# 6_laser_driver.net
KiCad netlist of a schematic drawn in Altium Designer
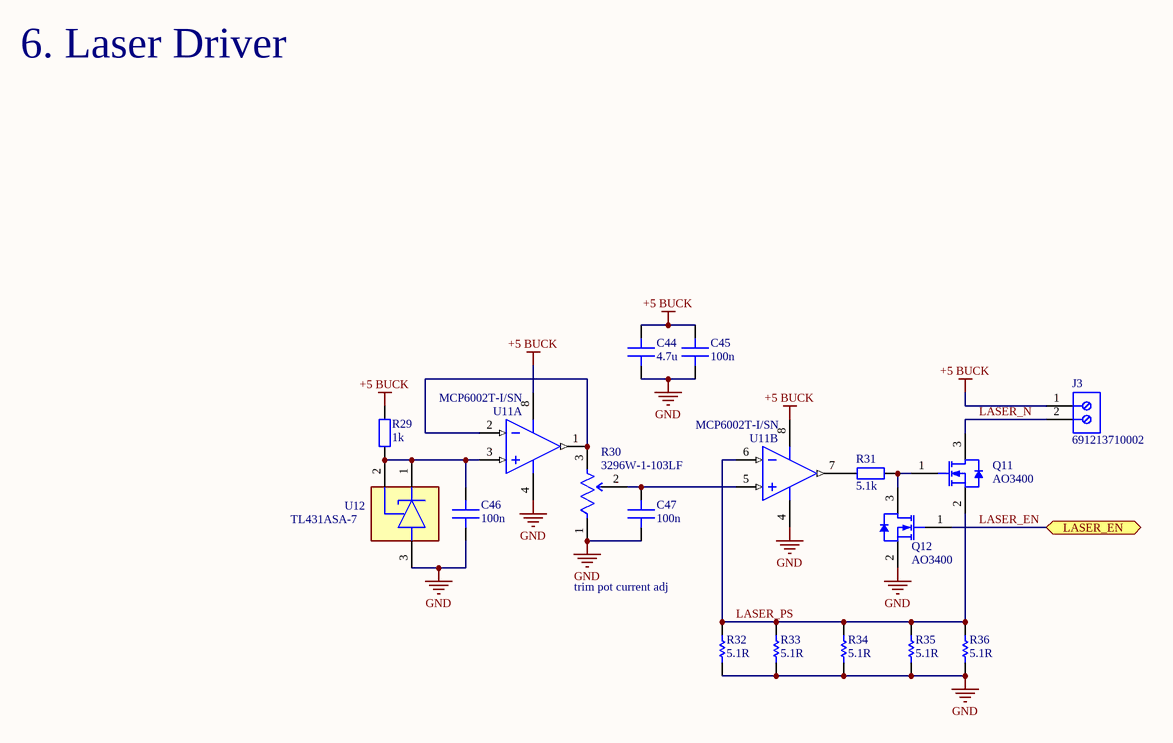
[diagram p0: 6_laser driver.SchDoc]

(export (version "E")
  (design (tool "Eeschema 10.0.6"))
  (components
    (comp (ref "C44")
      (value "4.7u")
      (footprint "IPC C C0603 NO SILK")
      (libsource (lib "JLCPCB Library") (part "Generic CAP 0603"))
    )
    (comp (ref "C45")
      (value "100n")
      (footprint "IPC C C0402 NO SILK")
      (libsource (lib "JLCPCB Library") (part "Generic CAP 0402"))
    )
    (comp (ref "C46")
      (value "100n")
      (footprint "IPC C C0402 NO SILK")
      (libsource (lib "JLCPCB Library") (part "Generic CAP 0402"))
    )
    (comp (ref "C47")
      (value "100n")
      (footprint "IPC C C0402 NO SILK")
      (libsource (lib "JLCPCB Library") (part "Generic CAP 0402"))
    )
    (comp (ref "J3")
      (value "691213710002")
      (footprint "691213710002")
      (fields (field (name "VOLTAGE") "300V"))
      (libsource (lib "Altium Content Vault") (part "TBL - 1R - 02P - Screw"))
    )
    (comp (ref "Q11")
      (value "AO3400")
      (footprint "AO-SOT23-3_V")
      (description "N-channel Enhancement Mode Field-Effect Transistor; 5.8A/30V")
      (fields (field (name "MANUFACTURER") "Alpha and Omega"))
      (libsource (lib "Altium Content Vault") (part "AO-NEMOS-G1S2D3-3"))
    )
    (comp (ref "Q12")
      (value "AO3400")
      (footprint "AO-SOT23-3_V")
      (description "N-channel Enhancement Mode Field-Effect Transistor; 5.8A/30V")
      (fields (field (name "MANUFACTURER") "Alpha and Omega"))
      (libsource (lib "Altium Content Vault") (part "AO-NEMOS-G1S2D3-3"))
    )
    (comp (ref "R29")
      (value "1k")
      (footprint "IPC C R0402 NO SILK")
      (libsource (lib "JLCPCB Library") (part "Generic RES 0402"))
    )
    (comp (ref "R30")
      (value "3296W-1-103LF")
      (footprint "FP-3296W-MFG")
      (description "TRIMMER 10K OHM 0.5W PC PIN TOP")
      (fields (field (name "TOLERANCE") "10%"))
      (libsource (lib "Altium Content Vault") (part "2dcfd2547301a7d3209a5e99acfd772"))
    )
    (comp (ref "R31")
      (value "5.1k")
      (footprint "IPC C R0402 NO SILK")
      (libsource (lib "JLCPCB Library") (part "Generic RES 0402"))
    )
    (comp (ref "R32")
      (value "5.1R")
      (footprint "RESC2013X70X40LL20T20")
      (fields (field (name "PART NUMBER") "ERJ-6GEYJ5R1V") (field (name "MANUFACTURER") "Panasonic"))
      (libsource (lib "Altium Content Vault") (part "RES"))
    )
    (comp (ref "R33")
      (value "5.1R")
      (footprint "RESC2013X70X40LL20T20")
      (fields (field (name "PART NUMBER") "ERJ-6GEYJ5R1V") (field (name "MANUFACTURER") "Panasonic"))
      (libsource (lib "Altium Content Vault") (part "RES"))
    )
    (comp (ref "R34")
      (value "5.1R")
      (footprint "RESC2013X70X40LL20T20")
      (fields (field (name "PART NUMBER") "ERJ-6GEYJ5R1V") (field (name "MANUFACTURER") "Panasonic"))
      (libsource (lib "Altium Content Vault") (part "RES"))
    )
    (comp (ref "R35")
      (value "5.1R")
      (footprint "RESC2013X70X40LL20T20")
      (fields (field (name "PART NUMBER") "ERJ-6GEYJ5R1V") (field (name "MANUFACTURER") "Panasonic"))
      (libsource (lib "Altium Content Vault") (part "RES"))
    )
    (comp (ref "R36")
      (value "5.1R")
      (footprint "RESC2013X70X40LL20T20")
      (fields (field (name "PART NUMBER") "ERJ-6GEYJ5R1V") (field (name "MANUFACTURER") "Panasonic"))
      (libsource (lib "Altium Content Vault") (part "RES"))
    )
    (comp (ref "U11")
      (value "MCP6002T-I/SN")
      (footprint "SOIC-SN8_N")
      (description "None")
      (libsource (lib "Altium Content Vault") (part "AMP-OPA-MCP6002-IL8"))
    )
    (comp (ref "U12")
      (value "TL431ASA-7")
      (footprint "FP-SOT23-MFG")
      (description "IC VREF SHUNT ADJ SOT23-3")
      (fields
        (field (name "OCTOPART") "https://octopart.com/tl431asa-7-diodes+inc.-18832779")
        (field (name "MANUFACTURER") "DIODES INC.")
      )
      (libsource (lib "Altium Content Vault") (part "bb7a1bf3cd7629b94a2ffd22ed0b9f9"))
    )
  )
  (nets
    (net (code "1") (name "+5 BUCK") (class "Default")
      (node (ref "C44") (pin "2") (pinfunction "2_2") (pintype "passive"))
      (node (ref "C45") (pin "2") (pinfunction "2_2") (pintype "passive"))
      (node (ref "J3") (pin "1") (pinfunction "1_1") (pintype "passive"))
      (node (ref "R29") (pin "2") (pinfunction "2_2") (pintype "passive"))
      (node (ref "U11") (pin "8") (pinfunction "VDD_8") (pintype "power_in"))
    )
    (net (code "2") (name "/LASER_EN") (class "Default")
      (node (ref "Q12") (pin "1") (pinfunction "G_1") (pintype "passive"))
    )
    (net (code "3") (name "/LASER_N") (class "Default")
      (node (ref "J3") (pin "2") (pinfunction "2_2") (pintype "passive"))
      (node (ref "Q11") (pin "3") (pinfunction "D_3") (pintype "passive"))
    )
    (net (code "4") (name "/LASER_PS") (class "Default")
      (node (ref "Q11") (pin "2") (pinfunction "S_2") (pintype "passive"))
      (node (ref "R32") (pin "2") (pinfunction "2_2") (pintype "passive"))
      (node (ref "R33") (pin "2") (pinfunction "2_2") (pintype "passive"))
      (node (ref "R34") (pin "2") (pinfunction "2_2") (pintype "passive"))
      (node (ref "R35") (pin "2") (pinfunction "2_2") (pintype "passive"))
      (node (ref "R36") (pin "2") (pinfunction "2_2") (pintype "passive"))
      (node (ref "U11") (pin "6") (pinfunction "VINB-_6") (pintype "input"))
    )
    (net (code "5") (name "GND") (class "Default")
      (node (ref "C44") (pin "1") (pinfunction "1_1") (pintype "passive"))
      (node (ref "C45") (pin "1") (pinfunction "1_1") (pintype "passive"))
      (node (ref "C46") (pin "1") (pinfunction "1_1") (pintype "passive"))
      (node (ref "C47") (pin "1") (pinfunction "1_1") (pintype "passive"))
      (node (ref "Q12") (pin "2") (pinfunction "S_2") (pintype "passive"))
      (node (ref "R30") (pin "1") (pinfunction "CCW_1") (pintype "passive"))
      (node (ref "R32") (pin "1") (pinfunction "1_1") (pintype "passive"))
      (node (ref "R33") (pin "1") (pinfunction "1_1") (pintype "passive"))
      (node (ref "R34") (pin "1") (pinfunction "1_1") (pintype "passive"))
      (node (ref "R35") (pin "1") (pinfunction "1_1") (pintype "passive"))
      (node (ref "R36") (pin "1") (pinfunction "1_1") (pintype "passive"))
      (node (ref "U11") (pin "4") (pinfunction "VSS_4") (pintype "power_in"))
      (node (ref "U12") (pin "3") (pinfunction "A_3") (pintype "passive"))
    )
    (net (code "6") (name "Net-(Q11-G)") (class "Default")
      (node (ref "Q11") (pin "1") (pinfunction "G_1") (pintype "passive"))
      (node (ref "Q12") (pin "3") (pinfunction "D_3") (pintype "passive"))
      (node (ref "R31") (pin "2") (pinfunction "2_2") (pintype "passive"))
    )
    (net (code "7") (name "Net-(R30-CW)") (class "Default")
      (node (ref "R30") (pin "3") (pinfunction "CW_3") (pintype "passive"))
      (node (ref "U11") (pin "1") (pinfunction "VOUTA_1") (pintype "output"))
      (node (ref "U11") (pin "2") (pinfunction "VINA-_2") (pintype "input"))
    )
    (net (code "8") (name "Net-(R30-WIPER)") (class "Default")
      (node (ref "C47") (pin "2") (pinfunction "2_2") (pintype "passive"))
      (node (ref "R30") (pin "2") (pinfunction "WIPER_2") (pintype "passive"))
      (node (ref "U11") (pin "5") (pinfunction "VINB+_5") (pintype "input"))
    )
    (net (code "9") (name "Net-(U11A-VINA+)") (class "Default")
      (node (ref "C46") (pin "2") (pinfunction "2_2") (pintype "passive"))
      (node (ref "R29") (pin "1") (pinfunction "1_1") (pintype "passive"))
      (node (ref "U11") (pin "3") (pinfunction "VINA+_3") (pintype "input"))
      (node (ref "U12") (pin "1") (pinfunction "C_1") (pintype "passive"))
      (node (ref "U12") (pin "2") (pinfunction "REF_2") (pintype "passive"))
    )
    (net (code "10") (name "Net-(U11B-VOUTB)") (class "Default")
      (node (ref "R31") (pin "1") (pinfunction "1_1") (pintype "passive"))
      (node (ref "U11") (pin "7") (pinfunction "VOUTB_7") (pintype "output"))
    )
  )
)
